# SENSOR.net
KiCad netlist of a schematic drawn in Altium Designer
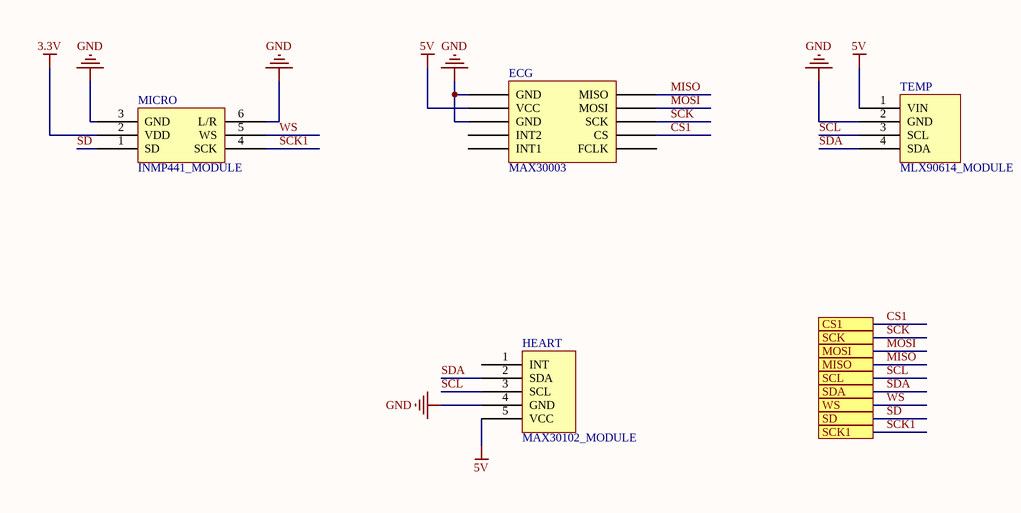
[diagram p0: SENSOR.SchDoc]

(export (version "E")
  (design (tool "Eeschema 10.0.6"))
  (components
    (comp (ref "ECG")
      (value "MAX30003")
      (footprint "MAX30003")
      (libsource (lib "KHOEMACH_LIB") (part "MAX30003"))
    )
    (comp (ref "HEART")
      (value "MAX30102_MODULE")
      (footprint "MAX30102_module")
      (libsource (lib "KHOEMACH_LIB") (part "MAX30102_MODULE"))
    )
    (comp (ref "MICRO")
      (value "INMP441_MODULE")
      (footprint "INMP441_MODULE")
      (libsource (lib "KHOEMACH_LIB") (part "INMP441_MODULE"))
    )
    (comp (ref "TEMP")
      (value "MLX90614_MODULE")
      (footprint "MLX90614_MODULE")
      (libsource (lib "KHOEMACH_LIB") (part "MLX90614_MODULE"))
    )
  )
  (nets
    (net (code "1") (name "/CS1") (class "Default")
      (node (ref "ECG") (pin "CS") (pinfunction "CS_CS") (pintype "passive"))
    )
    (net (code "2") (name "/MISO") (class "Default")
      (node (ref "ECG") (pin "MISO") (pinfunction "MISO_MISO") (pintype "passive"))
    )
    (net (code "3") (name "/MOSI") (class "Default")
      (node (ref "ECG") (pin "MOSI") (pinfunction "MOSI_MOSI") (pintype "passive"))
    )
    (net (code "4") (name "/SCK") (class "Default")
      (node (ref "ECG") (pin "SCK") (pinfunction "SCK_SCK") (pintype "passive"))
    )
    (net (code "5") (name "/SCK1") (class "Default")
      (node (ref "MICRO") (pin "4") (pinfunction "SCK_4") (pintype "passive"))
    )
    (net (code "6") (name "/SCL") (class "Default")
      (node (ref "HEART") (pin "3") (pinfunction "SCL_3") (pintype "passive"))
      (node (ref "TEMP") (pin "3") (pinfunction "SCL_3") (pintype "passive"))
    )
    (net (code "7") (name "/SD") (class "Default")
      (node (ref "MICRO") (pin "1") (pinfunction "SD_1") (pintype "passive"))
    )
    (net (code "8") (name "/SDA") (class "Default")
      (node (ref "HEART") (pin "2") (pinfunction "SDA_2") (pintype "passive"))
      (node (ref "TEMP") (pin "4") (pinfunction "SDA_4") (pintype "passive"))
    )
    (net (code "9") (name "/WS") (class "Default")
      (node (ref "MICRO") (pin "5") (pinfunction "WS_5") (pintype "passive"))
    )
    (net (code "10") (name "3.3V") (class "Default")
      (node (ref "MICRO") (pin "2") (pinfunction "VDD_2") (pintype "passive"))
    )
    (net (code "11") (name "5V") (class "Default")
      (node (ref "ECG") (pin "VCC") (pinfunction "VCC_VCC") (pintype "passive"))
      (node (ref "HEART") (pin "5") (pinfunction "VCC_5") (pintype "passive"))
      (node (ref "TEMP") (pin "1") (pinfunction "VIN_1") (pintype "passive"))
    )
    (net (code "12") (name "GND") (class "Default")
      (node (ref "ECG") (pin "GND") (pinfunction "GND_GND") (pintype "passive"))
      (node (ref "HEART") (pin "4") (pinfunction "GND_4") (pintype "passive"))
      (node (ref "MICRO") (pin "3") (pinfunction "GND_3") (pintype "passive"))
      (node (ref "MICRO") (pin "6") (pinfunction "L/R_6") (pintype "passive"))
      (node (ref "TEMP") (pin "2") (pinfunction "GND_2") (pintype "passive"))
    )
    (net (code "13") (name "unconnected-(ECG-PadFCLK)") (class "Default")
      (node (ref "ECG") (pin "FCLK") (pinfunction "FCLK_FCLK") (pintype "passive"))
    )
    (net (code "14") (name "unconnected-(ECG-PadINT1)") (class "Default")
      (node (ref "ECG") (pin "INT1") (pinfunction "INT1_INT1") (pintype "passive"))
    )
    (net (code "15") (name "unconnected-(ECG-PadINT2)") (class "Default")
      (node (ref "ECG") (pin "INT2") (pinfunction "INT2_INT2") (pintype "passive"))
    )
    (net (code "16") (name "unconnected-(HEART-INT-Pad1)") (class "Default")
      (node (ref "HEART") (pin "1") (pinfunction "INT_1") (pintype "passive"))
    )
  )
)
